# plinkykeeb_21Jan2022.net
KiCad netlist of a schematic drawn in EAGLE
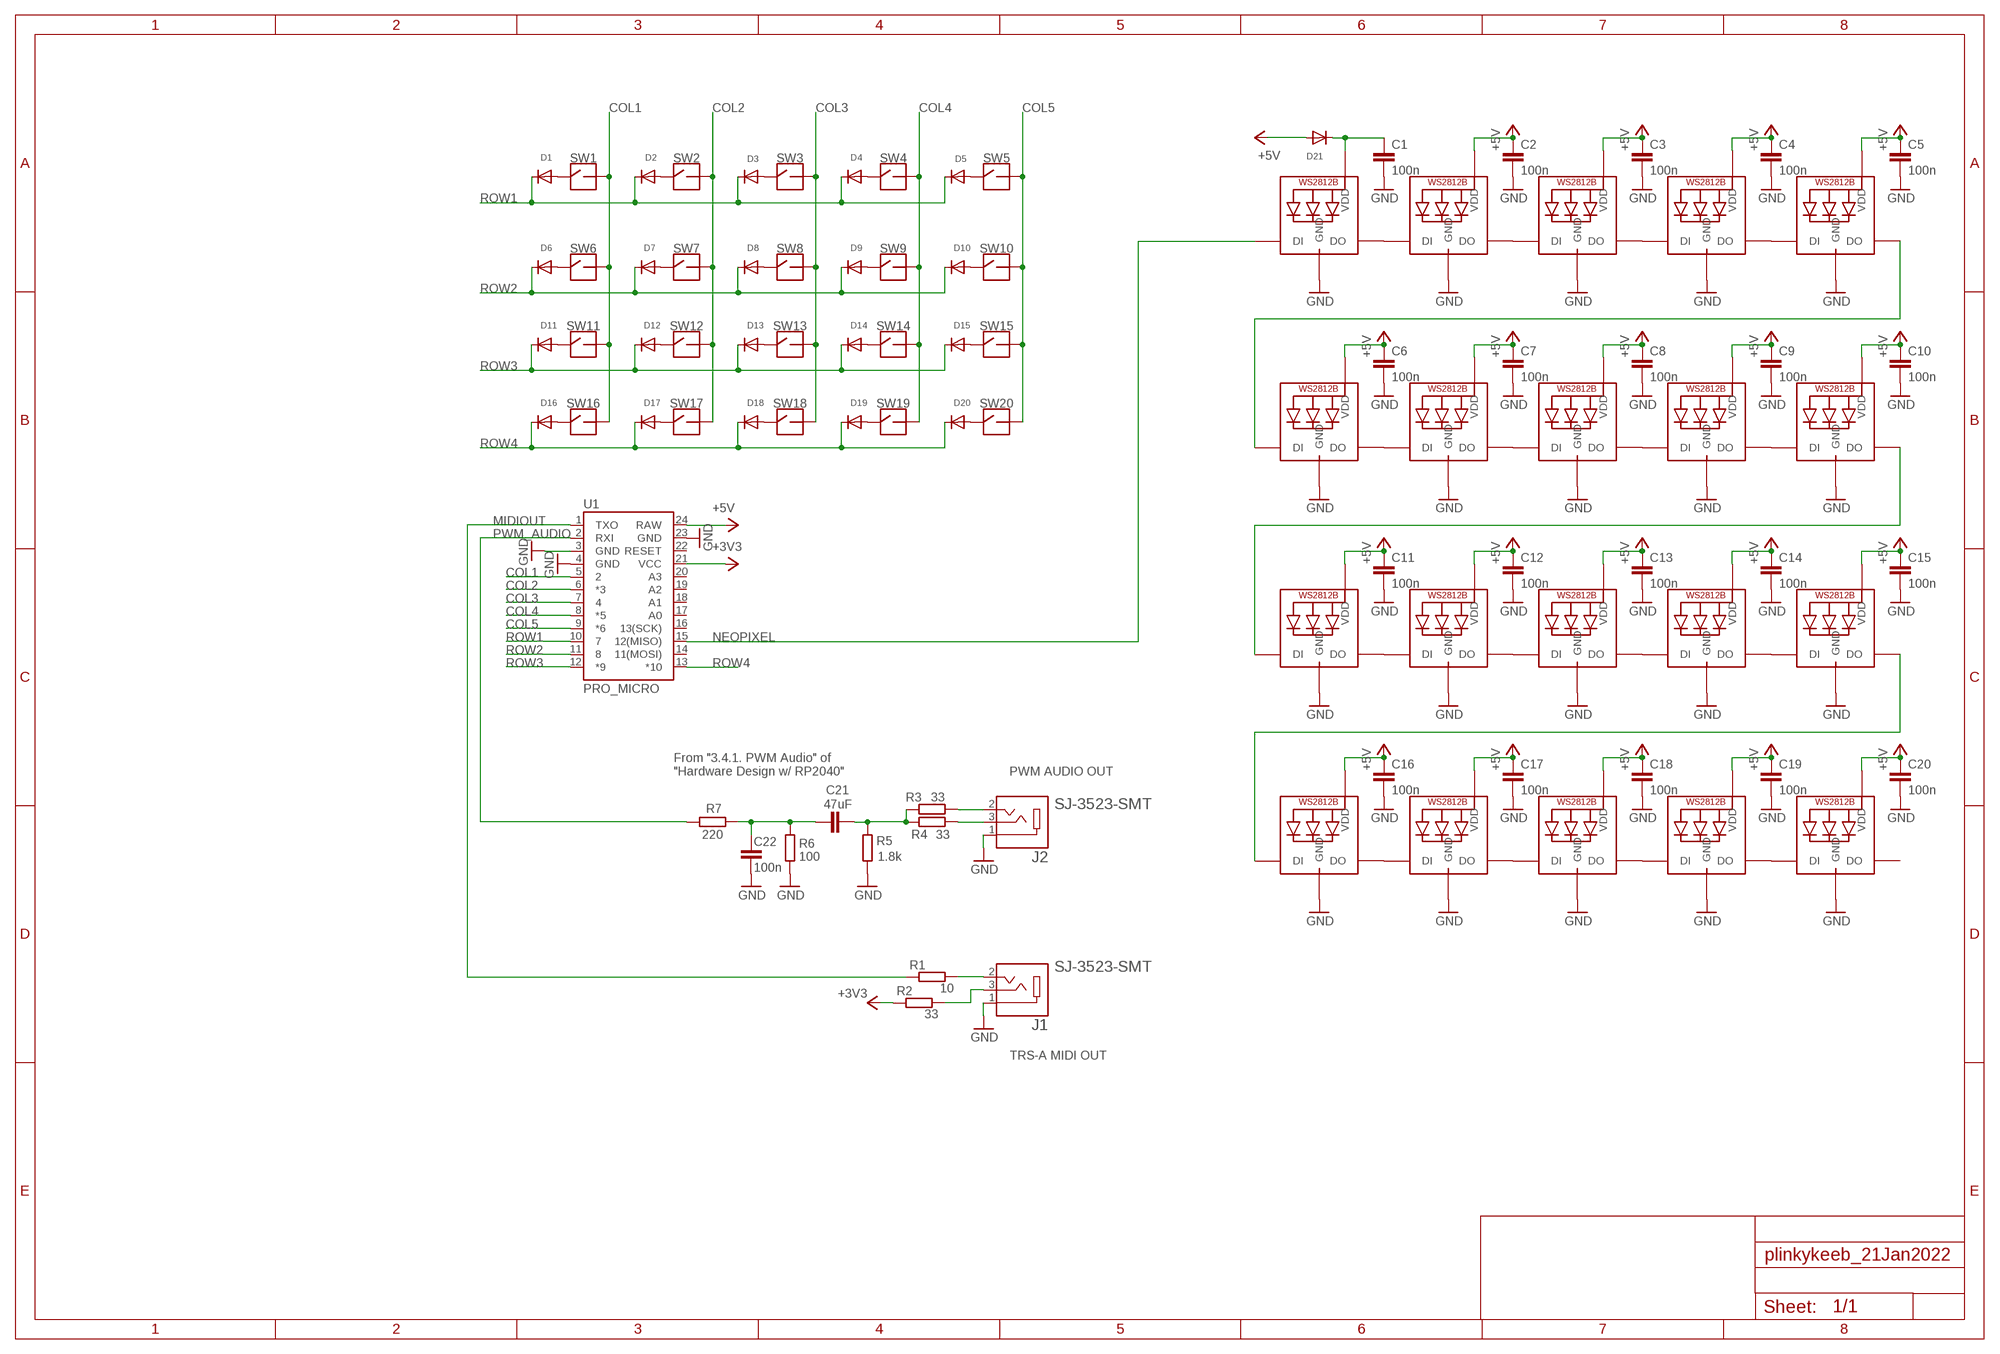
[diagram p0: schematic, sheet 1]

(export (version "E")
  (design (tool "Eeschema 10.0.6"))
  (components
    (comp (ref "C1")
      (value "100n")
      (footprint "eagle-import:C025-024X044")
      (libsource (lib "eagle-import") (part "C-EU025-024X044"))
    )
    (comp (ref "C2")
      (value "100n")
      (footprint "eagle-import:C025-024X044")
      (libsource (lib "eagle-import") (part "C-EU025-024X044"))
    )
    (comp (ref "C3")
      (value "100n")
      (footprint "eagle-import:C025-024X044")
      (libsource (lib "eagle-import") (part "C-EU025-024X044"))
    )
    (comp (ref "C4")
      (value "100n")
      (footprint "eagle-import:C025-024X044")
      (libsource (lib "eagle-import") (part "C-EU025-024X044"))
    )
    (comp (ref "C5")
      (value "100n")
      (footprint "eagle-import:C025-024X044")
      (libsource (lib "eagle-import") (part "C-EU025-024X044"))
    )
    (comp (ref "C6")
      (value "100n")
      (footprint "eagle-import:C025-024X044")
      (libsource (lib "eagle-import") (part "C-EU025-024X044"))
    )
    (comp (ref "C7")
      (value "100n")
      (footprint "eagle-import:C025-024X044")
      (libsource (lib "eagle-import") (part "C-EU025-024X044"))
    )
    (comp (ref "C8")
      (value "100n")
      (footprint "eagle-import:C025-024X044")
      (libsource (lib "eagle-import") (part "C-EU025-024X044"))
    )
    (comp (ref "C9")
      (value "100n")
      (footprint "eagle-import:C025-024X044")
      (libsource (lib "eagle-import") (part "C-EU025-024X044"))
    )
    (comp (ref "C10")
      (value "100n")
      (footprint "eagle-import:C025-024X044")
      (libsource (lib "eagle-import") (part "C-EU025-024X044"))
    )
    (comp (ref "C11")
      (value "100n")
      (footprint "eagle-import:C025-024X044")
      (libsource (lib "eagle-import") (part "C-EU025-024X044"))
    )
    (comp (ref "C12")
      (value "100n")
      (footprint "eagle-import:C025-024X044")
      (libsource (lib "eagle-import") (part "C-EU025-024X044"))
    )
    (comp (ref "C13")
      (value "100n")
      (footprint "eagle-import:C025-024X044")
      (libsource (lib "eagle-import") (part "C-EU025-024X044"))
    )
    (comp (ref "C14")
      (value "100n")
      (footprint "eagle-import:C025-024X044")
      (libsource (lib "eagle-import") (part "C-EU025-024X044"))
    )
    (comp (ref "C15")
      (value "100n")
      (footprint "eagle-import:C025-024X044")
      (libsource (lib "eagle-import") (part "C-EU025-024X044"))
    )
    (comp (ref "C16")
      (value "100n")
      (footprint "eagle-import:C025-024X044")
      (libsource (lib "eagle-import") (part "C-EU025-024X044"))
    )
    (comp (ref "C17")
      (value "100n")
      (footprint "eagle-import:C025-024X044")
      (libsource (lib "eagle-import") (part "C-EU025-024X044"))
    )
    (comp (ref "C18")
      (value "100n")
      (footprint "eagle-import:C025-024X044")
      (libsource (lib "eagle-import") (part "C-EU025-024X044"))
    )
    (comp (ref "C19")
      (value "100n")
      (footprint "eagle-import:C025-024X044")
      (libsource (lib "eagle-import") (part "C-EU025-024X044"))
    )
    (comp (ref "C20")
      (value "100n")
      (footprint "eagle-import:C025-024X044")
      (libsource (lib "eagle-import") (part "C-EU025-024X044"))
    )
    (comp (ref "C21")
      (value "47uF")
      (footprint "eagle-import:C0805")
      (libsource (lib "eagle-import") (part "C-EUC0805"))
    )
    (comp (ref "C22")
      (value "100n")
      (footprint "eagle-import:C0805")
      (libsource (lib "eagle-import") (part "C-EUC0805"))
    )
    (comp (ref "D1")
      (value "DIODEDO-1N4148")
      (footprint "eagle-import:DO-1N4148")
      (libsource (lib "eagle-import") (part "DIODEDO-1N4148"))
    )
    (comp (ref "D2")
      (value "DIODEDO-1N4148")
      (footprint "eagle-import:DO-1N4148")
      (libsource (lib "eagle-import") (part "DIODEDO-1N4148"))
    )
    (comp (ref "D3")
      (value "DIODEDO-1N4148")
      (footprint "eagle-import:DO-1N4148")
      (libsource (lib "eagle-import") (part "DIODEDO-1N4148"))
    )
    (comp (ref "D4")
      (value "DIODEDO-1N4148")
      (footprint "eagle-import:DO-1N4148")
      (libsource (lib "eagle-import") (part "DIODEDO-1N4148"))
    )
    (comp (ref "D5")
      (value "DIODEDO-1N4148")
      (footprint "eagle-import:DO-1N4148")
      (libsource (lib "eagle-import") (part "DIODEDO-1N4148"))
    )
    (comp (ref "D6")
      (value "DIODEDO-1N4148")
      (footprint "eagle-import:DO-1N4148")
      (libsource (lib "eagle-import") (part "DIODEDO-1N4148"))
    )
    (comp (ref "D7")
      (value "DIODEDO-1N4148")
      (footprint "eagle-import:DO-1N4148")
      (libsource (lib "eagle-import") (part "DIODEDO-1N4148"))
    )
    (comp (ref "D8")
      (value "DIODEDO-1N4148")
      (footprint "eagle-import:DO-1N4148")
      (libsource (lib "eagle-import") (part "DIODEDO-1N4148"))
    )
    (comp (ref "D9")
      (value "DIODEDO-1N4148")
      (footprint "eagle-import:DO-1N4148")
      (libsource (lib "eagle-import") (part "DIODEDO-1N4148"))
    )
    (comp (ref "D10")
      (value "DIODEDO-1N4148")
      (footprint "eagle-import:DO-1N4148")
      (libsource (lib "eagle-import") (part "DIODEDO-1N4148"))
    )
    (comp (ref "D11")
      (value "DIODEDO-1N4148")
      (footprint "eagle-import:DO-1N4148")
      (libsource (lib "eagle-import") (part "DIODEDO-1N4148"))
    )
    (comp (ref "D12")
      (value "DIODEDO-1N4148")
      (footprint "eagle-import:DO-1N4148")
      (libsource (lib "eagle-import") (part "DIODEDO-1N4148"))
    )
    (comp (ref "D13")
      (value "DIODEDO-1N4148")
      (footprint "eagle-import:DO-1N4148")
      (libsource (lib "eagle-import") (part "DIODEDO-1N4148"))
    )
    (comp (ref "D14")
      (value "DIODEDO-1N4148")
      (footprint "eagle-import:DO-1N4148")
      (libsource (lib "eagle-import") (part "DIODEDO-1N4148"))
    )
    (comp (ref "D15")
      (value "DIODEDO-1N4148")
      (footprint "eagle-import:DO-1N4148")
      (libsource (lib "eagle-import") (part "DIODEDO-1N4148"))
    )
    (comp (ref "D16")
      (value "DIODEDO-1N4148")
      (footprint "eagle-import:DO-1N4148")
      (libsource (lib "eagle-import") (part "DIODEDO-1N4148"))
    )
    (comp (ref "D17")
      (value "DIODEDO-1N4148")
      (footprint "eagle-import:DO-1N4148")
      (libsource (lib "eagle-import") (part "DIODEDO-1N4148"))
    )
    (comp (ref "D18")
      (value "DIODEDO-1N4148")
      (footprint "eagle-import:DO-1N4148")
      (libsource (lib "eagle-import") (part "DIODEDO-1N4148"))
    )
    (comp (ref "D19")
      (value "DIODEDO-1N4148")
      (footprint "eagle-import:DO-1N4148")
      (libsource (lib "eagle-import") (part "DIODEDO-1N4148"))
    )
    (comp (ref "D20")
      (value "DIODEDO-1N4148")
      (footprint "eagle-import:DO-1N4148")
      (libsource (lib "eagle-import") (part "DIODEDO-1N4148"))
    )
    (comp (ref "D21")
      (value "DIODEDO-1N4148")
      (footprint "eagle-import:DO-1N4148")
      (libsource (lib "eagle-import") (part "DIODEDO-1N4148"))
    )
    (comp (ref "J1")
      (value "SJ-3523-SMT")
      (footprint "eagle-import:CUI_SJ-3523-SMT")
      (fields
        (field (name "DIGI-KEY_PART_NUMBER") "CP-3523SJCT-ND")
        (field (name "MF") "CUI Devices")
        (field (name "MP") "SJ-3523-SMT-TR")
      )
      (libsource (lib "eagle-import") (part "SJ-3523-SMT"))
    )
    (comp (ref "J2")
      (value "SJ-3523-SMT")
      (footprint "eagle-import:CUI_SJ-3523-SMT")
      (fields
        (field (name "DIGI-KEY_PART_NUMBER") "CP-3523SJCT-ND")
        (field (name "MF") "CUI Devices")
        (field (name "MP") "SJ-3523-SMT-TR")
      )
      (libsource (lib "eagle-import") (part "SJ-3523-SMT"))
    )
    (comp (ref "LED1")
      (value "MICROBUILDER_WS2812B_SK6812E")
      (footprint "eagle-import:MICROBUILDER_NEO3535_REVERSE")
      (libsource (lib "eagle-import") (part "MICROBUILDER_WS2812B_SK6812E"))
    )
    (comp (ref "LED2")
      (value "MICROBUILDER_WS2812B_SK6812E")
      (footprint "eagle-import:MICROBUILDER_NEO3535_REVERSE")
      (libsource (lib "eagle-import") (part "MICROBUILDER_WS2812B_SK6812E"))
    )
    (comp (ref "LED3")
      (value "MICROBUILDER_WS2812B_SK6812E")
      (footprint "eagle-import:MICROBUILDER_NEO3535_REVERSE")
      (libsource (lib "eagle-import") (part "MICROBUILDER_WS2812B_SK6812E"))
    )
    (comp (ref "LED4")
      (value "MICROBUILDER_WS2812B_SK6812E")
      (footprint "eagle-import:MICROBUILDER_NEO3535_REVERSE")
      (libsource (lib "eagle-import") (part "MICROBUILDER_WS2812B_SK6812E"))
    )
    (comp (ref "LED5")
      (value "MICROBUILDER_WS2812B_SK6812E")
      (footprint "eagle-import:MICROBUILDER_NEO3535_REVERSE")
      (libsource (lib "eagle-import") (part "MICROBUILDER_WS2812B_SK6812E"))
    )
    (comp (ref "LED6")
      (value "MICROBUILDER_WS2812B_SK6812E")
      (footprint "eagle-import:MICROBUILDER_NEO3535_REVERSE")
      (libsource (lib "eagle-import") (part "MICROBUILDER_WS2812B_SK6812E"))
    )
    (comp (ref "LED7")
      (value "MICROBUILDER_WS2812B_SK6812E")
      (footprint "eagle-import:MICROBUILDER_NEO3535_REVERSE")
      (libsource (lib "eagle-import") (part "MICROBUILDER_WS2812B_SK6812E"))
    )
    (comp (ref "LED8")
      (value "MICROBUILDER_WS2812B_SK6812E")
      (footprint "eagle-import:MICROBUILDER_NEO3535_REVERSE")
      (libsource (lib "eagle-import") (part "MICROBUILDER_WS2812B_SK6812E"))
    )
    (comp (ref "LED9")
      (value "MICROBUILDER_WS2812B_SK6812E")
      (footprint "eagle-import:MICROBUILDER_NEO3535_REVERSE")
      (libsource (lib "eagle-import") (part "MICROBUILDER_WS2812B_SK6812E"))
    )
    (comp (ref "LED10")
      (value "MICROBUILDER_WS2812B_SK6812E")
      (footprint "eagle-import:MICROBUILDER_NEO3535_REVERSE")
      (libsource (lib "eagle-import") (part "MICROBUILDER_WS2812B_SK6812E"))
    )
    (comp (ref "LED11")
      (value "MICROBUILDER_WS2812B_SK6812E")
      (footprint "eagle-import:MICROBUILDER_NEO3535_REVERSE")
      (libsource (lib "eagle-import") (part "MICROBUILDER_WS2812B_SK6812E"))
    )
    (comp (ref "LED12")
      (value "MICROBUILDER_WS2812B_SK6812E")
      (footprint "eagle-import:MICROBUILDER_NEO3535_REVERSE")
      (libsource (lib "eagle-import") (part "MICROBUILDER_WS2812B_SK6812E"))
    )
    (comp (ref "LED13")
      (value "MICROBUILDER_WS2812B_SK6812E")
      (footprint "eagle-import:MICROBUILDER_NEO3535_REVERSE")
      (libsource (lib "eagle-import") (part "MICROBUILDER_WS2812B_SK6812E"))
    )
    (comp (ref "LED14")
      (value "MICROBUILDER_WS2812B_SK6812E")
      (footprint "eagle-import:MICROBUILDER_NEO3535_REVERSE")
      (libsource (lib "eagle-import") (part "MICROBUILDER_WS2812B_SK6812E"))
    )
    (comp (ref "LED15")
      (value "MICROBUILDER_WS2812B_SK6812E")
      (footprint "eagle-import:MICROBUILDER_NEO3535_REVERSE")
      (libsource (lib "eagle-import") (part "MICROBUILDER_WS2812B_SK6812E"))
    )
    (comp (ref "LED16")
      (value "MICROBUILDER_WS2812B_SK6812E")
      (footprint "eagle-import:MICROBUILDER_NEO3535_REVERSE")
      (libsource (lib "eagle-import") (part "MICROBUILDER_WS2812B_SK6812E"))
    )
    (comp (ref "LED17")
      (value "MICROBUILDER_WS2812B_SK6812E")
      (footprint "eagle-import:MICROBUILDER_NEO3535_REVERSE")
      (libsource (lib "eagle-import") (part "MICROBUILDER_WS2812B_SK6812E"))
    )
    (comp (ref "LED18")
      (value "MICROBUILDER_WS2812B_SK6812E")
      (footprint "eagle-import:MICROBUILDER_NEO3535_REVERSE")
      (libsource (lib "eagle-import") (part "MICROBUILDER_WS2812B_SK6812E"))
    )
    (comp (ref "LED19")
      (value "MICROBUILDER_WS2812B_SK6812E")
      (footprint "eagle-import:MICROBUILDER_NEO3535_REVERSE")
      (libsource (lib "eagle-import") (part "MICROBUILDER_WS2812B_SK6812E"))
    )
    (comp (ref "LED20")
      (value "MICROBUILDER_WS2812B_SK6812E")
      (footprint "eagle-import:MICROBUILDER_NEO3535_REVERSE")
      (libsource (lib "eagle-import") (part "MICROBUILDER_WS2812B_SK6812E"))
    )
    (comp (ref "R1")
      (value "10")
      (footprint "eagle-import:R0805")
      (libsource (lib "eagle-import") (part "R-EU_R0805"))
    )
    (comp (ref "R2")
      (value "33")
      (footprint "eagle-import:R0805")
      (libsource (lib "eagle-import") (part "R-EU_R0805"))
    )
    (comp (ref "R3")
      (value "33")
      (footprint "eagle-import:R0805")
      (libsource (lib "eagle-import") (part "R-EU_R0805"))
    )
    (comp (ref "R4")
      (value "33")
      (footprint "eagle-import:R0805")
      (libsource (lib "eagle-import") (part "R-EU_R0805"))
    )
    (comp (ref "R5")
      (value "1.8k")
      (footprint "eagle-import:R0805")
      (libsource (lib "eagle-import") (part "R-EU_R0805"))
    )
    (comp (ref "R6")
      (value "100")
      (footprint "eagle-import:R0805")
      (libsource (lib "eagle-import") (part "R-EU_R0805"))
    )
    (comp (ref "R7")
      (value "220")
      (footprint "eagle-import:R0805")
      (libsource (lib "eagle-import") (part "R-EU_R0805"))
    )
    (comp (ref "SW1")
      (value "KAILH_SOCKETBOX_JADE")
      (footprint "eagle-import:ADAFRUIT_ELECTROMECH_KAILH_SOCKET")
      (libsource (lib "eagle-import") (part "ADAFRUIT_ELECTROMECH_KBD_SWITCH_KAILH_SOCKETBOX_JADE_KAILH_SOCKET"))
    )
    (comp (ref "SW2")
      (value "KAILH_SOCKETBOX_JADE")
      (footprint "eagle-import:ADAFRUIT_ELECTROMECH_KAILH_SOCKET")
      (libsource (lib "eagle-import") (part "ADAFRUIT_ELECTROMECH_KBD_SWITCH_KAILH_SOCKETBOX_JADE_KAILH_SOCKET"))
    )
    (comp (ref "SW3")
      (value "KAILH_SOCKETBOX_JADE")
      (footprint "eagle-import:ADAFRUIT_ELECTROMECH_KAILH_SOCKET")
      (libsource (lib "eagle-import") (part "ADAFRUIT_ELECTROMECH_KBD_SWITCH_KAILH_SOCKETBOX_JADE_KAILH_SOCKET"))
    )
    (comp (ref "SW4")
      (value "KAILH_SOCKETBOX_JADE")
      (footprint "eagle-import:ADAFRUIT_ELECTROMECH_KAILH_SOCKET")
      (libsource (lib "eagle-import") (part "ADAFRUIT_ELECTROMECH_KBD_SWITCH_KAILH_SOCKETBOX_JADE_KAILH_SOCKET"))
    )
    (comp (ref "SW5")
      (value "KAILH_SOCKETBOX_JADE")
      (footprint "eagle-import:ADAFRUIT_ELECTROMECH_KAILH_SOCKET")
      (libsource (lib "eagle-import") (part "ADAFRUIT_ELECTROMECH_KBD_SWITCH_KAILH_SOCKETBOX_JADE_KAILH_SOCKET"))
    )
    (comp (ref "SW6")
      (value "KAILH_SOCKETBOX_JADE")
      (footprint "eagle-import:ADAFRUIT_ELECTROMECH_KAILH_SOCKET")
      (libsource (lib "eagle-import") (part "ADAFRUIT_ELECTROMECH_KBD_SWITCH_KAILH_SOCKETBOX_JADE_KAILH_SOCKET"))
    )
    (comp (ref "SW7")
      (value "KAILH_SOCKETBOX_JADE")
      (footprint "eagle-import:ADAFRUIT_ELECTROMECH_KAILH_SOCKET")
      (libsource (lib "eagle-import") (part "ADAFRUIT_ELECTROMECH_KBD_SWITCH_KAILH_SOCKETBOX_JADE_KAILH_SOCKET"))
    )
    (comp (ref "SW8")
      (value "KAILH_SOCKETBOX_JADE")
      (footprint "eagle-import:ADAFRUIT_ELECTROMECH_KAILH_SOCKET")
      (libsource (lib "eagle-import") (part "ADAFRUIT_ELECTROMECH_KBD_SWITCH_KAILH_SOCKETBOX_JADE_KAILH_SOCKET"))
    )
    (comp (ref "SW9")
      (value "KAILH_SOCKETBOX_JADE")
      (footprint "eagle-import:ADAFRUIT_ELECTROMECH_KAILH_SOCKET")
      (libsource (lib "eagle-import") (part "ADAFRUIT_ELECTROMECH_KBD_SWITCH_KAILH_SOCKETBOX_JADE_KAILH_SOCKET"))
    )
    (comp (ref "SW10")
      (value "KAILH_SOCKETBOX_JADE")
      (footprint "eagle-import:ADAFRUIT_ELECTROMECH_KAILH_SOCKET")
      (libsource (lib "eagle-import") (part "ADAFRUIT_ELECTROMECH_KBD_SWITCH_KAILH_SOCKETBOX_JADE_KAILH_SOCKET"))
    )
    (comp (ref "SW11")
      (value "KAILH_SOCKETBOX_JADE")
      (footprint "eagle-import:ADAFRUIT_ELECTROMECH_KAILH_SOCKET")
      (libsource (lib "eagle-import") (part "ADAFRUIT_ELECTROMECH_KBD_SWITCH_KAILH_SOCKETBOX_JADE_KAILH_SOCKET"))
    )
    (comp (ref "SW12")
      (value "KAILH_SOCKETBOX_JADE")
      (footprint "eagle-import:ADAFRUIT_ELECTROMECH_KAILH_SOCKET")
      (libsource (lib "eagle-import") (part "ADAFRUIT_ELECTROMECH_KBD_SWITCH_KAILH_SOCKETBOX_JADE_KAILH_SOCKET"))
    )
    (comp (ref "SW13")
      (value "KAILH_SOCKETBOX_JADE")
      (footprint "eagle-import:ADAFRUIT_ELECTROMECH_KAILH_SOCKET")
      (libsource (lib "eagle-import") (part "ADAFRUIT_ELECTROMECH_KBD_SWITCH_KAILH_SOCKETBOX_JADE_KAILH_SOCKET"))
    )
    (comp (ref "SW14")
      (value "KAILH_SOCKETBOX_JADE")
      (footprint "eagle-import:ADAFRUIT_ELECTROMECH_KAILH_SOCKET")
      (libsource (lib "eagle-import") (part "ADAFRUIT_ELECTROMECH_KBD_SWITCH_KAILH_SOCKETBOX_JADE_KAILH_SOCKET"))
    )
    (comp (ref "SW15")
      (value "KAILH_SOCKETBOX_JADE")
      (footprint "eagle-import:ADAFRUIT_ELECTROMECH_KAILH_SOCKET")
      (libsource (lib "eagle-import") (part "ADAFRUIT_ELECTROMECH_KBD_SWITCH_KAILH_SOCKETBOX_JADE_KAILH_SOCKET"))
    )
    (comp (ref "SW16")
      (value "KAILH_SOCKETBOX_JADE")
      (footprint "eagle-import:ADAFRUIT_ELECTROMECH_KAILH_SOCKET")
      (libsource (lib "eagle-import") (part "ADAFRUIT_ELECTROMECH_KBD_SWITCH_KAILH_SOCKETBOX_JADE_KAILH_SOCKET"))
    )
    (comp (ref "SW17")
      (value "KAILH_SOCKETBOX_JADE")
      (footprint "eagle-import:ADAFRUIT_ELECTROMECH_KAILH_SOCKET")
      (libsource (lib "eagle-import") (part "ADAFRUIT_ELECTROMECH_KBD_SWITCH_KAILH_SOCKETBOX_JADE_KAILH_SOCKET"))
    )
    (comp (ref "SW18")
      (value "KAILH_SOCKETBOX_JADE")
      (footprint "eagle-import:ADAFRUIT_ELECTROMECH_KAILH_SOCKET")
      (libsource (lib "eagle-import") (part "ADAFRUIT_ELECTROMECH_KBD_SWITCH_KAILH_SOCKETBOX_JADE_KAILH_SOCKET"))
    )
    (comp (ref "SW19")
      (value "KAILH_SOCKETBOX_JADE")
      (footprint "eagle-import:ADAFRUIT_ELECTROMECH_KAILH_SOCKET")
      (libsource (lib "eagle-import") (part "ADAFRUIT_ELECTROMECH_KBD_SWITCH_KAILH_SOCKETBOX_JADE_KAILH_SOCKET"))
    )
    (comp (ref "SW20")
      (value "KAILH_SOCKETBOX_JADE")
      (footprint "eagle-import:ADAFRUIT_ELECTROMECH_KAILH_SOCKET")
      (libsource (lib "eagle-import") (part "ADAFRUIT_ELECTROMECH_KBD_SWITCH_KAILH_SOCKETBOX_JADE_KAILH_SOCKET"))
    )
    (comp (ref "U1")
      (value "PRO_MICRO")
      (footprint "eagle-import:SPARKFUN_PRO_MICRO")
      (libsource (lib "eagle-import") (part "SPARKFUN_PRO_MICRO"))
    )
  )
  (nets
    (net (code "1") (name "+3V3") (class "Default")
      (node (ref "R2") (pin "2") (pinfunction "2_2") (pintype "passive"))
      (node (ref "U1") (pin "21") (pinfunction "VCC_21") (pintype "power_in"))
    )
    (net (code "2") (name "+5V") (class "Default")
      (node (ref "C10") (pin "1") (pinfunction "1_1") (pintype "passive"))
      (node (ref "C11") (pin "1") (pinfunction "1_1") (pintype "passive"))
      (node (ref "C12") (pin "1") (pinfunction "1_1") (pintype "passive"))
      (node (ref "C13") (pin "1") (pinfunction "1_1") (pintype "passive"))
      (node (ref "C14") (pin "1") (pinfunction "1_1") (pintype "passive"))
      (node (ref "C15") (pin "1") (pinfunction "1_1") (pintype "passive"))
      (node (ref "C16") (pin "1") (pinfunction "1_1") (pintype "passive"))
      (node (ref "C17") (pin "1") (pinfunction "1_1") (pintype "passive"))
      (node (ref "C18") (pin "1") (pinfunction "1_1") (pintype "passive"))
      (node (ref "C19") (pin "1") (pinfunction "1_1") (pintype "passive"))
      (node (ref "C2") (pin "1") (pinfunction "1_1") (pintype "passive"))
      (node (ref "C20") (pin "1") (pinfunction "1_1") (pintype "passive"))
      (node (ref "C3") (pin "1") (pinfunction "1_1") (pintype "passive"))
      (node (ref "C4") (pin "1") (pinfunction "1_1") (pintype "passive"))
      (node (ref "C5") (pin "1") (pinfunction "1_1") (pintype "passive"))
      (node (ref "C6") (pin "1") (pinfunction "1_1") (pintype "passive"))
      (node (ref "C7") (pin "1") (pinfunction "1_1") (pintype "passive"))
      (node (ref "C8") (pin "1") (pinfunction "1_1") (pintype "passive"))
      (node (ref "C9") (pin "1") (pinfunction "1_1") (pintype "passive"))
      (node (ref "D21") (pin "A") (pinfunction "A_A") (pintype "passive"))
      (node (ref "LED10") (pin "1-VDD") (pinfunction "VDD_1-VDD") (pintype "power_in"))
      (node (ref "LED11") (pin "1-VDD") (pinfunction "VDD_1-VDD") (pintype "power_in"))
      (node (ref "LED12") (pin "1-VDD") (pinfunction "VDD_1-VDD") (pintype "power_in"))
      (node (ref "LED13") (pin "1-VDD") (pinfunction "VDD_1-VDD") (pintype "power_in"))
      (node (ref "LED14") (pin "1-VDD") (pinfunction "VDD_1-VDD") (pintype "power_in"))
      (node (ref "LED15") (pin "1-VDD") (pinfunction "VDD_1-VDD") (pintype "power_in"))
      (node (ref "LED16") (pin "1-VDD") (pinfunction "VDD_1-VDD") (pintype "power_in"))
      (node (ref "LED17") (pin "1-VDD") (pinfunction "VDD_1-VDD") (pintype "power_in"))
      (node (ref "LED18") (pin "1-VDD") (pinfunction "VDD_1-VDD") (pintype "power_in"))
      (node (ref "LED19") (pin "1-VDD") (pinfunction "VDD_1-VDD") (pintype "power_in"))
      (node (ref "LED2") (pin "1-VDD") (pinfunction "VDD_1-VDD") (pintype "power_in"))
      (node (ref "LED20") (pin "1-VDD") (pinfunction "VDD_1-VDD") (pintype "power_in"))
      (node (ref "LED3") (pin "1-VDD") (pinfunction "VDD_1-VDD") (pintype "power_in"))
      (node (ref "LED4") (pin "1-VDD") (pinfunction "VDD_1-VDD") (pintype "power_in"))
      (node (ref "LED5") (pin "1-VDD") (pinfunction "VDD_1-VDD") (pintype "power_in"))
      (node (ref "LED6") (pin "1-VDD") (pinfunction "VDD_1-VDD") (pintype "power_in"))
      (node (ref "LED7") (pin "1-VDD") (pinfunction "VDD_1-VDD") (pintype "power_in"))
      (node (ref "LED8") (pin "1-VDD") (pinfunction "VDD_1-VDD") (pintype "power_in"))
      (node (ref "LED9") (pin "1-VDD") (pinfunction "VDD_1-VDD") (pintype "power_in"))
      (node (ref "U1") (pin "24") (pinfunction "RAW_24") (pintype "power_in"))
    )
    (net (code "3") (name "/COL1") (class "Default")
      (node (ref "SW1") (pin "2") (pinfunction "2_2") (pintype "passive"))
      (node (ref "SW11") (pin "2") (pinfunction "2_2") (pintype "passive"))
      (node (ref "SW16") (pin "2") (pinfunction "2_2") (pintype "passive"))
      (node (ref "SW6") (pin "2") (pinfunction "2_2") (pintype "passive"))
      (node (ref "U1") (pin "5") (pinfunction "2_5") (pintype "bidirectional"))
    )
    (net (code "4") (name "/COL2") (class "Default")
      (node (ref "SW12") (pin "2") (pinfunction "2_2") (pintype "passive"))
      (node (ref "SW17") (pin "2") (pinfunction "2_2") (pintype "passive"))
      (node (ref "SW2") (pin "2") (pinfunction "2_2") (pintype "passive"))
      (node (ref "SW7") (pin "2") (pinfunction "2_2") (pintype "passive"))
      (node (ref "U1") (pin "6") (pinfunction "*3_6") (pintype "bidirectional"))
    )
    (net (code "5") (name "/COL3") (class "Default")
      (node (ref "SW13") (pin "2") (pinfunction "2_2") (pintype "passive"))
      (node (ref "SW18") (pin "2") (pinfunction "2_2") (pintype "passive"))
      (node (ref "SW3") (pin "2") (pinfunction "2_2") (pintype "passive"))
      (node (ref "SW8") (pin "2") (pinfunction "2_2") (pintype "passive"))
      (node (ref "U1") (pin "7") (pinfunction "4_7") (pintype "bidirectional"))
    )
    (net (code "6") (name "/COL4") (class "Default")
      (node (ref "SW14") (pin "2") (pinfunction "2_2") (pintype "passive"))
      (node (ref "SW19") (pin "2") (pinfunction "2_2") (pintype "passive"))
      (node (ref "SW4") (pin "2") (pinfunction "2_2") (pintype "passive"))
      (node (ref "SW9") (pin "2") (pinfunction "2_2") (pintype "passive"))
      (node (ref "U1") (pin "8") (pinfunction "*5_8") (pintype "bidirectional"))
    )
    (net (code "7") (name "/COL5") (class "Default")
      (node (ref "SW10") (pin "2") (pinfunction "2_2") (pintype "passive"))
      (node (ref "SW15") (pin "2") (pinfunction "2_2") (pintype "passive"))
      (node (ref "SW20") (pin "2") (pinfunction "2_2") (pintype "passive"))
      (node (ref "SW5") (pin "2") (pinfunction "2_2") (pintype "passive"))
      (node (ref "U1") (pin "9") (pinfunction "*6_9") (pintype "bidirectional"))
    )
    (net (code "8") (name "/MIDIOUT") (class "Default")
      (node (ref "R1") (pin "2") (pinfunction "2_2") (pintype "passive"))
      (node (ref "U1") (pin "1") (pinfunction "TXO_1") (pintype "bidirectional"))
    )
    (net (code "9") (name "/NEOPIXEL") (class "Default")
      (node (ref "LED1") (pin "4-DIN") (pinfunction "DI_4-DIN") (pintype "input"))
      (node (ref "U1") (pin "15") (pinfunction "12(MISO)_15") (pintype "bidirectional"))
    )
    (net (code "10") (name "/PWM_AUDIO") (class "Default")
      (node (ref "R7") (pin "2") (pinfunction "2_2") (pintype "passive"))
      (node (ref "U1") (pin "2") (pinfunction "RXI_2") (pintype "bidirectional"))
    )
    (net (code "11") (name "/ROW1") (class "Default")
      (node (ref "D1") (pin "C") (pinfunction "C_C") (pintype "passive"))
      (node (ref "D2") (pin "C") (pinfunction "C_C") (pintype "passive"))
      (node (ref "D3") (pin "C") (pinfunction "C_C") (pintype "passive"))
      (node (ref "D4") (pin "C") (pinfunction "C_C") (pintype "passive"))
      (node (ref "D5") (pin "C") (pinfunction "C_C") (pintype "passive"))
      (node (ref "U1") (pin "10") (pinfunction "7_10") (pintype "bidirectional"))
    )
    (net (code "12") (name "/ROW2") (class "Default")
      (node (ref "D10") (pin "C") (pinfunction "C_C") (pintype "passive"))
      (node (ref "D6") (pin "C") (pinfunction "C_C") (pintype "passive"))
      (node (ref "D7") (pin "C") (pinfunction "C_C") (pintype "passive"))
      (node (ref "D8") (pin "C") (pinfunction "C_C") (pintype "passive"))
      (node (ref "D9") (pin "C") (pinfunction "C_C") (pintype "passive"))
      (node (ref "U1") (pin "11") (pinfunction "8_11") (pintype "bidirectional"))
    )
    (net (code "13") (name "/ROW3") (class "Default")
      (node (ref "D11") (pin "C") (pinfunction "C_C") (pintype "passive"))
      (node (ref "D12") (pin "C") (pinfunction "C_C") (pintype "passive"))
      (node (ref "D13") (pin "C") (pinfunction "C_C") (pintype "passive"))
      (node (ref "D14") (pin "C") (pinfunction "C_C") (pintype "passive"))
      (node (ref "D15") (pin "C") (pinfunction "C_C") (pintype "passive"))
      (node (ref "U1") (pin "12") (pinfunction "*9_12") (pintype "bidirectional"))
    )
    (net (code "14") (name "/ROW4") (class "Default")
      (node (ref "D16") (pin "C") (pinfunction "C_C") (pintype "passive"))
      (node (ref "D17") (pin "C") (pinfunction "C_C") (pintype "passive"))
      (node (ref "D18") (pin "C") (pinfunction "C_C") (pintype "passive"))
      (node (ref "D19") (pin "C") (pinfunction "C_C") (pintype "passive"))
      (node (ref "D20") (pin "C") (pinfunction "C_C") (pintype "passive"))
      (node (ref "U1") (pin "13") (pinfunction "*10_13") (pintype "bidirectional"))
    )
    (net (code "15") (name "GND") (class "Default")
      (node (ref "C1") (pin "2") (pinfunction "2_2") (pintype "passive"))
      (node (ref "C10") (pin "2") (pinfunction "2_2") (pintype "passive"))
      (node (ref "C11") (pin "2") (pinfunction "2_2") (pintype "passive"))
      (node (ref "C12") (pin "2") (pinfunction "2_2") (pintype "passive"))
      (node (ref "C13") (pin "2") (pinfunction "2_2") (pintype "passive"))
      (node (ref "C14") (pin "2") (pinfunction "2_2") (pintype "passive"))
      (node (ref "C15") (pin "2") (pinfunction "2_2") (pintype "passive"))
      (node (ref "C16") (pin "2") (pinfunction "2_2") (pintype "passive"))
      (node (ref "C17") (pin "2") (pinfunction "2_2") (pintype "passive"))
      (node (ref "C18") (pin "2") (pinfunction "2_2") (pintype "passive"))
      (node (ref "C19") (pin "2") (pinfunction "2_2") (pintype "passive"))
      (node (ref "C2") (pin "2") (pinfunction "2_2") (pintype "passive"))
      (node (ref "C20") (pin "2") (pinfunction "2_2") (pintype "passive"))
      (node (ref "C22") (pin "2") (pinfunction "2_2") (pintype "passive"))
      (node (ref "C3") (pin "2") (pinfunction "2_2") (pintype "passive"))
      (node (ref "C4") (pin "2") (pinfunction "2_2") (pintype "passive"))
      (node (ref "C5") (pin "2") (pinfunction "2_2") (pintype "passive"))
      (node (ref "C6") (pin "2") (pinfunction "2_2") (pintype "passive"))
      (node (ref "C7") (pin "2") (pinfunction "2_2") (pintype "passive"))
      (node (ref "C8") (pin "2") (pinfunction "2_2") (pintype "passive"))
      (node (ref "C9") (pin "2") (pinfunction "2_2") (pintype "passive"))
      (node (ref "J1") (pin "1") (pinfunction "1_1") (pintype "passive"))
      (node (ref "J2") (pin "1") (pinfunction "1_1") (pintype "passive"))
      (node (ref "LED1") (pin "3-GND") (pinfunction "GND_3-GND") (pintype "power_in"))
      (node (ref "LED10") (pin "3-GND") (pinfunction "GND_3-GND") (pintype "power_in"))
      (node (ref "LED11") (pin "3-GND") (pinfunction "GND_3-GND") (pintype "power_in"))
      (node (ref "LED12") (pin "3-GND") (pinfunction "GND_3-GND") (pintype "power_in"))
      (node (ref "LED13") (pin "3-GND") (pinfunction "GND_3-GND") (pintype "power_in"))
      (node (ref "LED14") (pin "3-GND") (pinfunction "GND_3-GND") (pintype "power_in"))
      (node (ref "LED15") (pin "3-GND") (pinfunction "GND_3-GND") (pintype "power_in"))
      (node (ref "LED16") (pin "3-GND") (pinfunction "GND_3-GND") (pintype "power_in"))
      (node (ref "LED17") (pin "3-GND") (pinfunction "GND_3-GND") (pintype "power_in"))
      (node (ref "LED18") (pin "3-GND") (pinfunction "GND_3-GND") (pintype "power_in"))
      (node (ref "LED19") (pin "3-GND") (pinfunction "GND_3-GND") (pintype "power_in"))
      (node (ref "LED2") (pin "3-GND") (pinfunction "GND_3-GND") (pintype "power_in"))
      (node (ref "LED20") (pin "3-GND") (pinfunction "GND_3-GND") (pintype "power_in"))
      (node (ref "LED3") (pin "3-GND") (pinfunction "GND_3-GND") (pintype "power_in"))
      (node (ref "LED4") (pin "3-GND") (pinfunction "GND_3-GND") (pintype "power_in"))
      (node (ref "LED5") (pin "3-GND") (pinfunction "GND_3-GND") (pintype "power_in"))
      (node (ref "LED6") (pin "3-GND") (pinfunction "GND_3-GND") (pintype "power_in"))
      (node (ref "LED7") (pin "3-GND") (pinfunction "GND_3-GND") (pintype "power_in"))
      (node (ref "LED8") (pin "3-GND") (pinfunction "GND_3-GND") (pintype "power_in"))
      (node (ref "LED9") (pin "3-GND") (pinfunction "GND_3-GND") (pintype "power_in"))
      (node (ref "R5") (pin "2") (pinfunction "2_2") (pintype "passive"))
      (node (ref "R6") (pin "1") (pinfunction "1_1") (pintype "passive"))
      (node (ref "U1") (pin "23") (pinfunction "GND_23") (pintype "power_in"))
      (node (ref "U1") (pin "3") (pinfunction "GND_3") (pintype "power_in"))
      (node (ref "U1") (pin "4") (pinfunction "GND_4") (pintype "power_in"))
    )
    (net (code "16") (name "Net-(C21-Pad1)") (class "Default")
      (node (ref "C21") (pin "1") (pinfunction "1_1") (pintype "passive"))
      (node (ref "C22") (pin "1") (pinfunction "1_1") (pintype "passive"))
      (node (ref "R6") (pin "2") (pinfunction "2_2") (pintype "passive"))
      (node (ref "R7") (pin "1") (pinfunction "1_1") (pintype "passive"))
    )
    (net (code "17") (name "Net-(C21-Pad2)") (class "Default")
      (node (ref "C21") (pin "2") (pinfunction "2_2") (pintype "passive"))
      (node (ref "R3") (pin "2") (pinfunction "2_2") (pintype "passive"))
      (node (ref "R4") (pin "2") (pinfunction "2_2") (pintype "passive"))
      (node (ref "R5") (pin "1") (pinfunction "1_1") (pintype "passive"))
    )
    (net (code "18") (name "Net-(D1-PadA)") (class "Default")
      (node (ref "D1") (pin "A") (pinfunction "A_A") (pintype "passive"))
      (node (ref "SW1") (pin "1") (pinfunction "1_1") (pintype "passive"))
    )
    (net (code "19") (name "Net-(D2-PadA)") (class "Default")
      (node (ref "D2") (pin "A") (pinfunction "A_A") (pintype "passive"))
      (node (ref "SW2") (pin "1") (pinfunction "1_1") (pintype "passive"))
    )
    (net (code "20") (name "Net-(D3-PadA)") (class "Default")
      (node (ref "D3") (pin "A") (pinfunction "A_A") (pintype "passive"))
      (node (ref "SW3") (pin "1") (pinfunction "1_1") (pintype "passive"))
    )
    (net (code "21") (name "Net-(D4-PadA)") (class "Default")
      (node (ref "D4") (pin "A") (pinfunction "A_A") (pintype "passive"))
      (node (ref "SW4") (pin "1") (pinfunction "1_1") (pintype "passive"))
    )
    (net (code "22") (name "Net-(D5-PadA)") (class "Default")
      (node (ref "D5") (pin "A") (pinfunction "A_A") (pintype "passive"))
      (node (ref "SW5") (pin "1") (pinfunction "1_1") (pintype "passive"))
    )
    (net (code "23") (name "Net-(D6-PadA)") (class "Default")
      (node (ref "D6") (pin "A") (pinfunction "A_A") (pintype "passive"))
      (node (ref "SW6") (pin "1") (pinfunction "1_1") (pintype "passive"))
    )
    (net (code "24") (name "Net-(D7-PadA)") (class "Default")
      (node (ref "D7") (pin "A") (pinfunction "A_A") (pintype "passive"))
      (node (ref "SW7") (pin "1") (pinfunction "1_1") (pintype "passive"))
    )
    (net (code "25") (name "Net-(D8-PadA)") (class "Default")
      (node (ref "D8") (pin "A") (pinfunction "A_A") (pintype "passive"))
      (node (ref "SW8") (pin "1") (pinfunction "1_1") (pintype "passive"))
    )
    (net (code "26") (name "Net-(D9-PadA)") (class "Default")
      (node (ref "D9") (pin "A") (pinfunction "A_A") (pintype "passive"))
      (node (ref "SW9") (pin "1") (pinfunction "1_1") (pintype "passive"))
    )
    (net (code "27") (name "Net-(D10-PadA)") (class "Default")
      (node (ref "D10") (pin "A") (pinfunction "A_A") (pintype "passive"))
      (node (ref "SW10") (pin "1") (pinfunction "1_1") (pintype "passive"))
    )
    (net (code "28") (name "Net-(D11-PadA)") (class "Default")
      (node (ref "D11") (pin "A") (pinfunction "A_A") (pintype "passive"))
      (node (ref "SW11") (pin "1") (pinfunction "1_1") (pintype "passive"))
    )
    (net (code "29") (name "Net-(D12-PadA)") (class "Default")
      (node (ref "D12") (pin "A") (pinfunction "A_A") (pintype "passive"))
      (node (ref "SW12") (pin "1") (pinfunction "1_1") (pintype "passive"))
    )
    (net (code "30") (name "Net-(D13-PadA)") (class "Default")
      (node (ref "D13") (pin "A") (pinfunction "A_A") (pintype "passive"))
      (node (ref "SW13") (pin "1") (pinfunction "1_1") (pintype "passive"))
    )
    (net (code "31") (name "Net-(D14-PadA)") (class "Default")
      (node (ref "D14") (pin "A") (pinfunction "A_A") (pintype "passive"))
      (node (ref "SW14") (pin "1") (pinfunction "1_1") (pintype "passive"))
    )
    (net (code "32") (name "Net-(D15-PadA)") (class "Default")
      (node (ref "D15") (pin "A") (pinfunction "A_A") (pintype "passive"))
      (node (ref "SW15") (pin "1") (pinfunction "1_1") (pintype "passive"))
    )
    (net (code "33") (name "Net-(D16-PadA)") (class "Default")
      (node (ref "D16") (pin "A") (pinfunction "A_A") (pintype "passive"))
      (node (ref "SW16") (pin "1") (pinfunction "1_1") (pintype "passive"))
    )
    (net (code "34") (name "Net-(D17-PadA)") (class "Default")
      (node (ref "D17") (pin "A") (pinfunction "A_A") (pintype "passive"))
      (node (ref "SW17") (pin "1") (pinfunction "1_1") (pintype "passive"))
    )
    (net (code "35") (name "Net-(D18-PadA)") (class "Default")
      (node (ref "D18") (pin "A") (pinfunction "A_A") (pintype "passive"))
      (node (ref "SW18") (pin "1") (pinfunction "1_1") (pintype "passive"))
    )
    (net (code "36") (name "Net-(D19-PadA)") (class "Default")
      (node (ref "D19") (pin "A") (pinfunction "A_A") (pintype "passive"))
      (node (ref "SW19") (pin "1") (pinfunction "1_1") (pintype "passive"))
    )
    (net (code "37") (name "Net-(D20-PadA)") (class "Default")
      (node (ref "D20") (pin "A") (pinfunction "A_A") (pintype "passive"))
      (node (ref "SW20") (pin "1") (pinfunction "1_1") (pintype "passive"))
    )
    (net (code "38") (name "Net-(J1-Pad2)") (class "Default")
      (node (ref "J1") (pin "2") (pinfunction "2_2") (pintype "passive"))
      (node (ref "R1") (pin "1") (pinfunction "1_1") (pintype "passive"))
    )
    (net (code "39") (name "Net-(J1-Pad3)") (class "Default")
      (node (ref "J1") (pin "3") (pinfunction "3_3") (pintype "passive"))
      (node (ref "R2") (pin "1") (pinfunction "1_1") (pintype "passive"))
    )
    (net (code "40") (name "Net-(J2-Pad2)") (class "Default")
      (node (ref "J2") (pin "2") (pinfunction "2_2") (pintype "passive"))
      (node (ref "R3") (pin "1") (pinfunction "1_1") (pintype "passive"))
    )
    (net (code "41") (name "Net-(J2-Pad3)") (class "Default")
      (node (ref "J2") (pin "3") (pinfunction "3_3") (pintype "passive"))
      (node (ref "R4") (pin "1") (pinfunction "1_1") (pintype "passive"))
    )
    (net (code "42") (name "Net-(LED1-DO)") (class "Default")
      (node (ref "LED1") (pin "2-DOUT") (pinfunction "DO_2-DOUT") (pintype "output"))
      (node (ref "LED2") (pin "4-DIN") (pinfunction "DI_4-DIN") (pintype "input"))
    )
    (net (code "43") (name "Net-(LED1-VDD)") (class "Default")
      (node (ref "C1") (pin "1") (pinfunction "1_1") (pintype "passive"))
      (node (ref "D21") (pin "C") (pinfunction "C_C") (pintype "passive"))
      (node (ref "LED1") (pin "1-VDD") (pinfunction "VDD_1-VDD") (pintype "power_in"))
    )
    (net (code "44") (name "Net-(LED2-DO)") (class "Default")
      (node (ref "LED2") (pin "2-DOUT") (pinfunction "DO_2-DOUT") (pintype "output"))
      (node (ref "LED3") (pin "4-DIN") (pinfunction "DI_4-DIN") (pintype "input"))
    )
    (net (code "45") (name "Net-(LED3-DO)") (class "Default")
      (node (ref "LED3") (pin "2-DOUT") (pinfunction "DO_2-DOUT") (pintype "output"))
      (node (ref "LED4") (pin "4-DIN") (pinfunction "DI_4-DIN") (pintype "input"))
    )
    (net (code "46") (name "Net-(LED4-DO)") (class "Default")
      (node (ref "LED4") (pin "2-DOUT") (pinfunction "DO_2-DOUT") (pintype "output"))
      (node (ref "LED5") (pin "4-DIN") (pinfunction "DI_4-DIN") (pintype "input"))
    )
    (net (code "47") (name "Net-(LED5-DO)") (class "Default")
      (node (ref "LED5") (pin "2-DOUT") (pinfunction "DO_2-DOUT") (pintype "output"))
      (node (ref "LED6") (pin "4-DIN") (pinfunction "DI_4-DIN") (pintype "input"))
    )
    (net (code "48") (name "Net-(LED6-DO)") (class "Default")
      (node (ref "LED6") (pin "2-DOUT") (pinfunction "DO_2-DOUT") (pintype "output"))
      (node (ref "LED7") (pin "4-DIN") (pinfunction "DI_4-DIN") (pintype "input"))
    )
    (net (code "49") (name "Net-(LED7-DO)") (class "Default")
      (node (ref "LED7") (pin "2-DOUT") (pinfunction "DO_2-DOUT") (pintype "output"))
      (node (ref "LED8") (pin "4-DIN") (pinfunction "DI_4-DIN") (pintype "input"))
    )
    (net (code "50") (name "Net-(LED8-DO)") (class "Default")
      (node (ref "LED8") (pin "2-DOUT") (pinfunction "DO_2-DOUT") (pintype "output"))
      (node (ref "LED9") (pin "4-DIN") (pinfunction "DI_4-DIN") (pintype "input"))
    )
    (net (code "51") (name "Net-(LED10-DI)") (class "Default")
      (node (ref "LED10") (pin "4-DIN") (pinfunction "DI_4-DIN") (pintype "input"))
      (node (ref "LED9") (pin "2-DOUT") (pinfunction "DO_2-DOUT") (pintype "output"))
    )
    (net (code "52") (name "Net-(LED10-DO)") (class "Default")
      (node (ref "LED10") (pin "2-DOUT") (pinfunction "DO_2-DOUT") (pintype "output"))
      (node (ref "LED11") (pin "4-DIN") (pinfunction "DI_4-DIN") (pintype "input"))
    )
    (net (code "53") (name "Net-(LED11-DO)") (class "Default")
      (node (ref "LED11") (pin "2-DOUT") (pinfunction "DO_2-DOUT") (pintype "output"))
      (node (ref "LED12") (pin "4-DIN") (pinfunction "DI_4-DIN") (pintype "input"))
    )
    (net (code "54") (name "Net-(LED12-DO)") (class "Default")
      (node (ref "LED12") (pin "2-DOUT") (pinfunction "DO_2-DOUT") (pintype "output"))
      (node (ref "LED13") (pin "4-DIN") (pinfunction "DI_4-DIN") (pintype "input"))
    )
    (net (code "55") (name "Net-(LED13-DO)") (class "Default")
      (node (ref "LED13") (pin "2-DOUT") (pinfunction "DO_2-DOUT") (pintype "output"))
      (node (ref "LED14") (pin "4-DIN") (pinfunction "DI_4-DIN") (pintype "input"))
    )
    (net (code "56") (name "Net-(LED14-DO)") (class "Default")
      (node (ref "LED14") (pin "2-DOUT") (pinfunction "DO_2-DOUT") (pintype "output"))
      (node (ref "LED15") (pin "4-DIN") (pinfunction "DI_4-DIN") (pintype "input"))
    )
    (net (code "57") (name "Net-(LED15-DO)") (class "Default")
      (node (ref "LED15") (pin "2-DOUT") (pinfunction "DO_2-DOUT") (pintype "output"))
      (node (ref "LED16") (pin "4-DIN") (pinfunction "DI_4-DIN") (pintype "input"))
    )
    (net (code "58") (name "Net-(LED16-DO)") (class "Default")
      (node (ref "LED16") (pin "2-DOUT") (pinfunction "DO_2-DOUT") (pintype "output"))
      (node (ref "LED17") (pin "4-DIN") (pinfunction "DI_4-DIN") (pintype "input"))
    )
    (net (code "59") (name "Net-(LED17-DO)") (class "Default")
      (node (ref "LED17") (pin "2-DOUT") (pinfunction "DO_2-DOUT") (pintype "output"))
      (node (ref "LED18") (pin "4-DIN") (pinfunction "DI_4-DIN") (pintype "input"))
    )
    (net (code "60") (name "Net-(LED18-DO)") (class "Default")
      (node (ref "LED18") (pin "2-DOUT") (pinfunction "DO_2-DOUT") (pintype "output"))
      (node (ref "LED19") (pin "4-DIN") (pinfunction "DI_4-DIN") (pintype "input"))
    )
    (net (code "61") (name "Net-(LED19-DO)") (class "Default")
      (node (ref "LED19") (pin "2-DOUT") (pinfunction "DO_2-DOUT") (pintype "output"))
      (node (ref "LED20") (pin "4-DIN") (pinfunction "DI_4-DIN") (pintype "input"))
    )
    (net (code "62") (name "unconnected-(LED20-DO-Pad2-DOUT)") (class "Default")
      (node (ref "LED20") (pin "2-DOUT") (pinfunction "DO_2-DOUT") (pintype "output"))
    )
    (net (code "63") (name "unconnected-(U1-11(MOSI)-Pad14)") (class "Default")
      (node (ref "U1") (pin "14") (pinfunction "11(MOSI)_14") (pintype "bidirectional"))
    )
    (net (code "64") (name "unconnected-(U1-13(SCK)-Pad16)") (class "Default")
      (node (ref "U1") (pin "16") (pinfunction "13(SCK)_16") (pintype "bidirectional"))
    )
    (net (code "65") (name "unconnected-(U1-A0-Pad17)") (class "Default")
      (node (ref "U1") (pin "17") (pinfunction "A0_17") (pintype "bidirectional"))
    )
    (net (code "66") (name "unconnected-(U1-A1-Pad18)") (class "Default")
      (node (ref "U1") (pin "18") (pinfunction "A1_18") (pintype "bidirectional"))
    )
    (net (code "67") (name "unconnected-(U1-A2-Pad19)") (class "Default")
      (node (ref "U1") (pin "19") (pinfunction "A2_19") (pintype "bidirectional"))
    )
    (net (code "68") (name "unconnected-(U1-A3-Pad20)") (class "Default")
      (node (ref "U1") (pin "20") (pinfunction "A3_20") (pintype "bidirectional"))
    )
    (net (code "69") (name "unconnected-(U1-RESET-Pad22)") (class "Default")
      (node (ref "U1") (pin "22") (pinfunction "RESET_22") (pintype "bidirectional"))
    )
  )
)
